# PowerBoard.net
KiCad netlist of a schematic drawn in Altium Designer
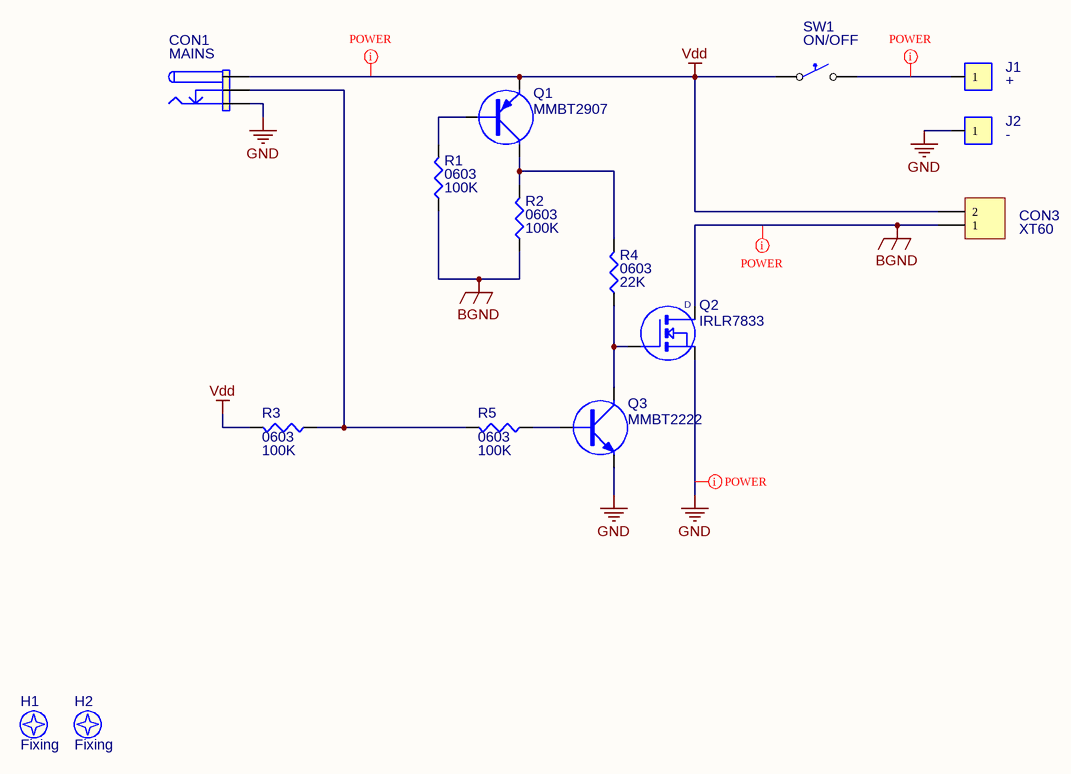
[diagram p0: PowerBoard.SchDoc]

(export (version "E")
  (design (tool "Eeschema 10.0.6"))
  (components
    (comp (ref "CON1")
      (value "MAINS")
      (footprint "PCB-DC-SOCKET")
      (description "Switched 2.5mm DC Connector - PCB")
      (libsource (lib "connectors") (part "DC2.5MM-PCBV(LB)"))
    )
    (comp (ref "CON3")
      (value "XT60")
      (footprint "CON-XT60")
      (description "XT60 Connector")
      (fields (field (name "PUBLISHER") "Altium Limited"))
      (libsource (lib "Miscellaneous Connectors") (part "XT60"))
    )
    (comp (ref "H1")
      (value "Fixing")
      (footprint "HW-FIXING-2.5MM-PLASTIC")
      (description "M3/M4 Fixing Hole")
      (libsource (lib "hardware") (part "HW-FIXING-ISOLATED(LB)"))
    )
    (comp (ref "H2")
      (value "Fixing")
      (footprint "HW-FIXING-2.5MM-PLASTIC")
      (description "M3/M4 Fixing Hole")
      (libsource (lib "hardware") (part "HW-FIXING-ISOLATED(LB)"))
    )
    (comp (ref "J1") (value "+") (footprint "TESTPOINT(LB)") (libsource (lib "connectors") (part "CON1(LB)")))
    (comp (ref "J2") (value "-") (footprint "TESTPOINT(LB)") (libsource (lib "connectors") (part "CON1(LB)")))
    (comp (ref "Q1")
      (value "MMBT2907")
      (footprint "SOT-23(LB)")
      (description "PNP Transistor")
      (libsource (lib "semi") (part "MMBT2907(SMD)"))
    )
    (comp (ref "Q2")
      (value "IRLR7833")
      (footprint "TO-252(LB)")
      (libsource (lib "semi") (part "IRLR7833(LB)"))
    )
    (comp (ref "Q3")
      (value "MMBT2222")
      (footprint "SOT-23(LB)")
      (description "NPN Transistor")
      (libsource (lib "semi") (part "MMBT2222(SMD)"))
    )
    (comp (ref "R1")
      (value "0603")
      (footprint "0603(LB)")
      (description "Resistor")
      (fields (field (name "ALTIUM_VALUE") "100K") (field (name "PUBLISHER") "Altium Limited"))
      (libsource (lib "Miscellaneous Devices") (part "Res3"))
    )
    (comp (ref "R2")
      (value "0603")
      (footprint "0603(LB)")
      (description "Resistor")
      (fields (field (name "ALTIUM_VALUE") "100K") (field (name "PUBLISHER") "Altium Limited"))
      (libsource (lib "Miscellaneous Devices") (part "Res3"))
    )
    (comp (ref "R3")
      (value "0603")
      (footprint "0603(LB)")
      (description "Resistor")
      (fields (field (name "ALTIUM_VALUE") "100K") (field (name "PUBLISHER") "Altium Limited"))
      (libsource (lib "Miscellaneous Devices") (part "Res3"))
    )
    (comp (ref "R4")
      (value "0603")
      (footprint "0603(LB)")
      (description "Resistor")
      (fields (field (name "ALTIUM_VALUE") "22K") (field (name "PUBLISHER") "Altium Limited"))
      (libsource (lib "Miscellaneous Devices") (part "Res3"))
    )
    (comp (ref "R5")
      (value "0603")
      (footprint "0603(LB)")
      (description "Resistor")
      (fields (field (name "ALTIUM_VALUE") "100K") (field (name "PUBLISHER") "Altium Limited"))
      (libsource (lib "Miscellaneous Devices") (part "Res3"))
    )
    (comp (ref "SW1")
      (value "ON/OFF")
      (footprint "PCB-SWSPDT-ROCKER")
      (description "Single-pole Single-throw Switch")
      (libsource (lib "switches") (part "SW-SPST(LB)"))
    )
  )
  (nets
    (net (code "1") (name "BGND") (class "Default")
      (node (ref "CON3") (pin "1") (pinfunction "1_1") (pintype "passive"))
      (node (ref "Q2") (pin "3") (pinfunction "D_3") (pintype "passive"))
      (node (ref "R1") (pin "1") (pinfunction "1_1") (pintype "passive"))
      (node (ref "R2") (pin "1") (pinfunction "1_1") (pintype "passive"))
    )
    (net (code "2") (name "GND") (class "Default")
      (node (ref "CON1") (pin "3") (pinfunction "Body_3") (pintype "power_in"))
      (node (ref "J2") (pin "1") (pinfunction "1_1") (pintype "passive"))
      (node (ref "Q2") (pin "2") (pinfunction "S_2") (pintype "passive"))
      (node (ref "Q3") (pin "2") (pinfunction "E_2") (pintype "passive"))
    )
    (net (code "3") (name "Net-(CON1-SWITCHED-BODY)") (class "Default")
      (node (ref "CON1") (pin "2") (pinfunction "SWITCHED-BODY_2") (pintype "power_in"))
      (node (ref "R3") (pin "1") (pinfunction "1_1") (pintype "passive"))
      (node (ref "R5") (pin "2") (pinfunction "2_2") (pintype "passive"))
    )
    (net (code "4") (name "Net-(Q1-B)") (class "Default")
      (node (ref "Q1") (pin "1") (pinfunction "B_1") (pintype "passive"))
      (node (ref "R1") (pin "2") (pinfunction "2_2") (pintype "passive"))
    )
    (net (code "5") (name "Net-(Q1-C)") (class "Default")
      (node (ref "Q1") (pin "3") (pinfunction "C_3") (pintype "passive"))
      (node (ref "R2") (pin "2") (pinfunction "2_2") (pintype "passive"))
      (node (ref "R4") (pin "2") (pinfunction "2_2") (pintype "passive"))
    )
    (net (code "6") (name "Net-(Q2-G)") (class "Default")
      (node (ref "Q2") (pin "1") (pinfunction "G_1") (pintype "passive"))
      (node (ref "Q3") (pin "3") (pinfunction "C_3") (pintype "passive"))
      (node (ref "R4") (pin "1") (pinfunction "1_1") (pintype "passive"))
    )
    (net (code "7") (name "Net-(Q3-B)") (class "Default")
      (node (ref "Q3") (pin "1") (pinfunction "B_1") (pintype "passive"))
      (node (ref "R5") (pin "1") (pinfunction "1_1") (pintype "passive"))
    )
    (net (code "8") (name "Net-(SW1-NO)") (class "Default")
      (node (ref "J1") (pin "1") (pinfunction "1_1") (pintype "passive"))
      (node (ref "SW1") (pin "2") (pinfunction "NO_2") (pintype "passive"))
    )
    (net (code "9") (name "Vdd") (class "Default")
      (node (ref "CON1") (pin "1") (pinfunction "TIP_1") (pintype "power_in"))
      (node (ref "CON3") (pin "2") (pinfunction "2_2") (pintype "passive"))
      (node (ref "Q1") (pin "2") (pinfunction "E_2") (pintype "passive"))
      (node (ref "R3") (pin "2") (pinfunction "2_2") (pintype "passive"))
      (node (ref "SW1") (pin "1") (pinfunction "COM_1") (pintype "passive"))
    )
  )
)
